# ProtoBricks_8x8.net
KiCad netlist of a schematic drawn in EAGLE
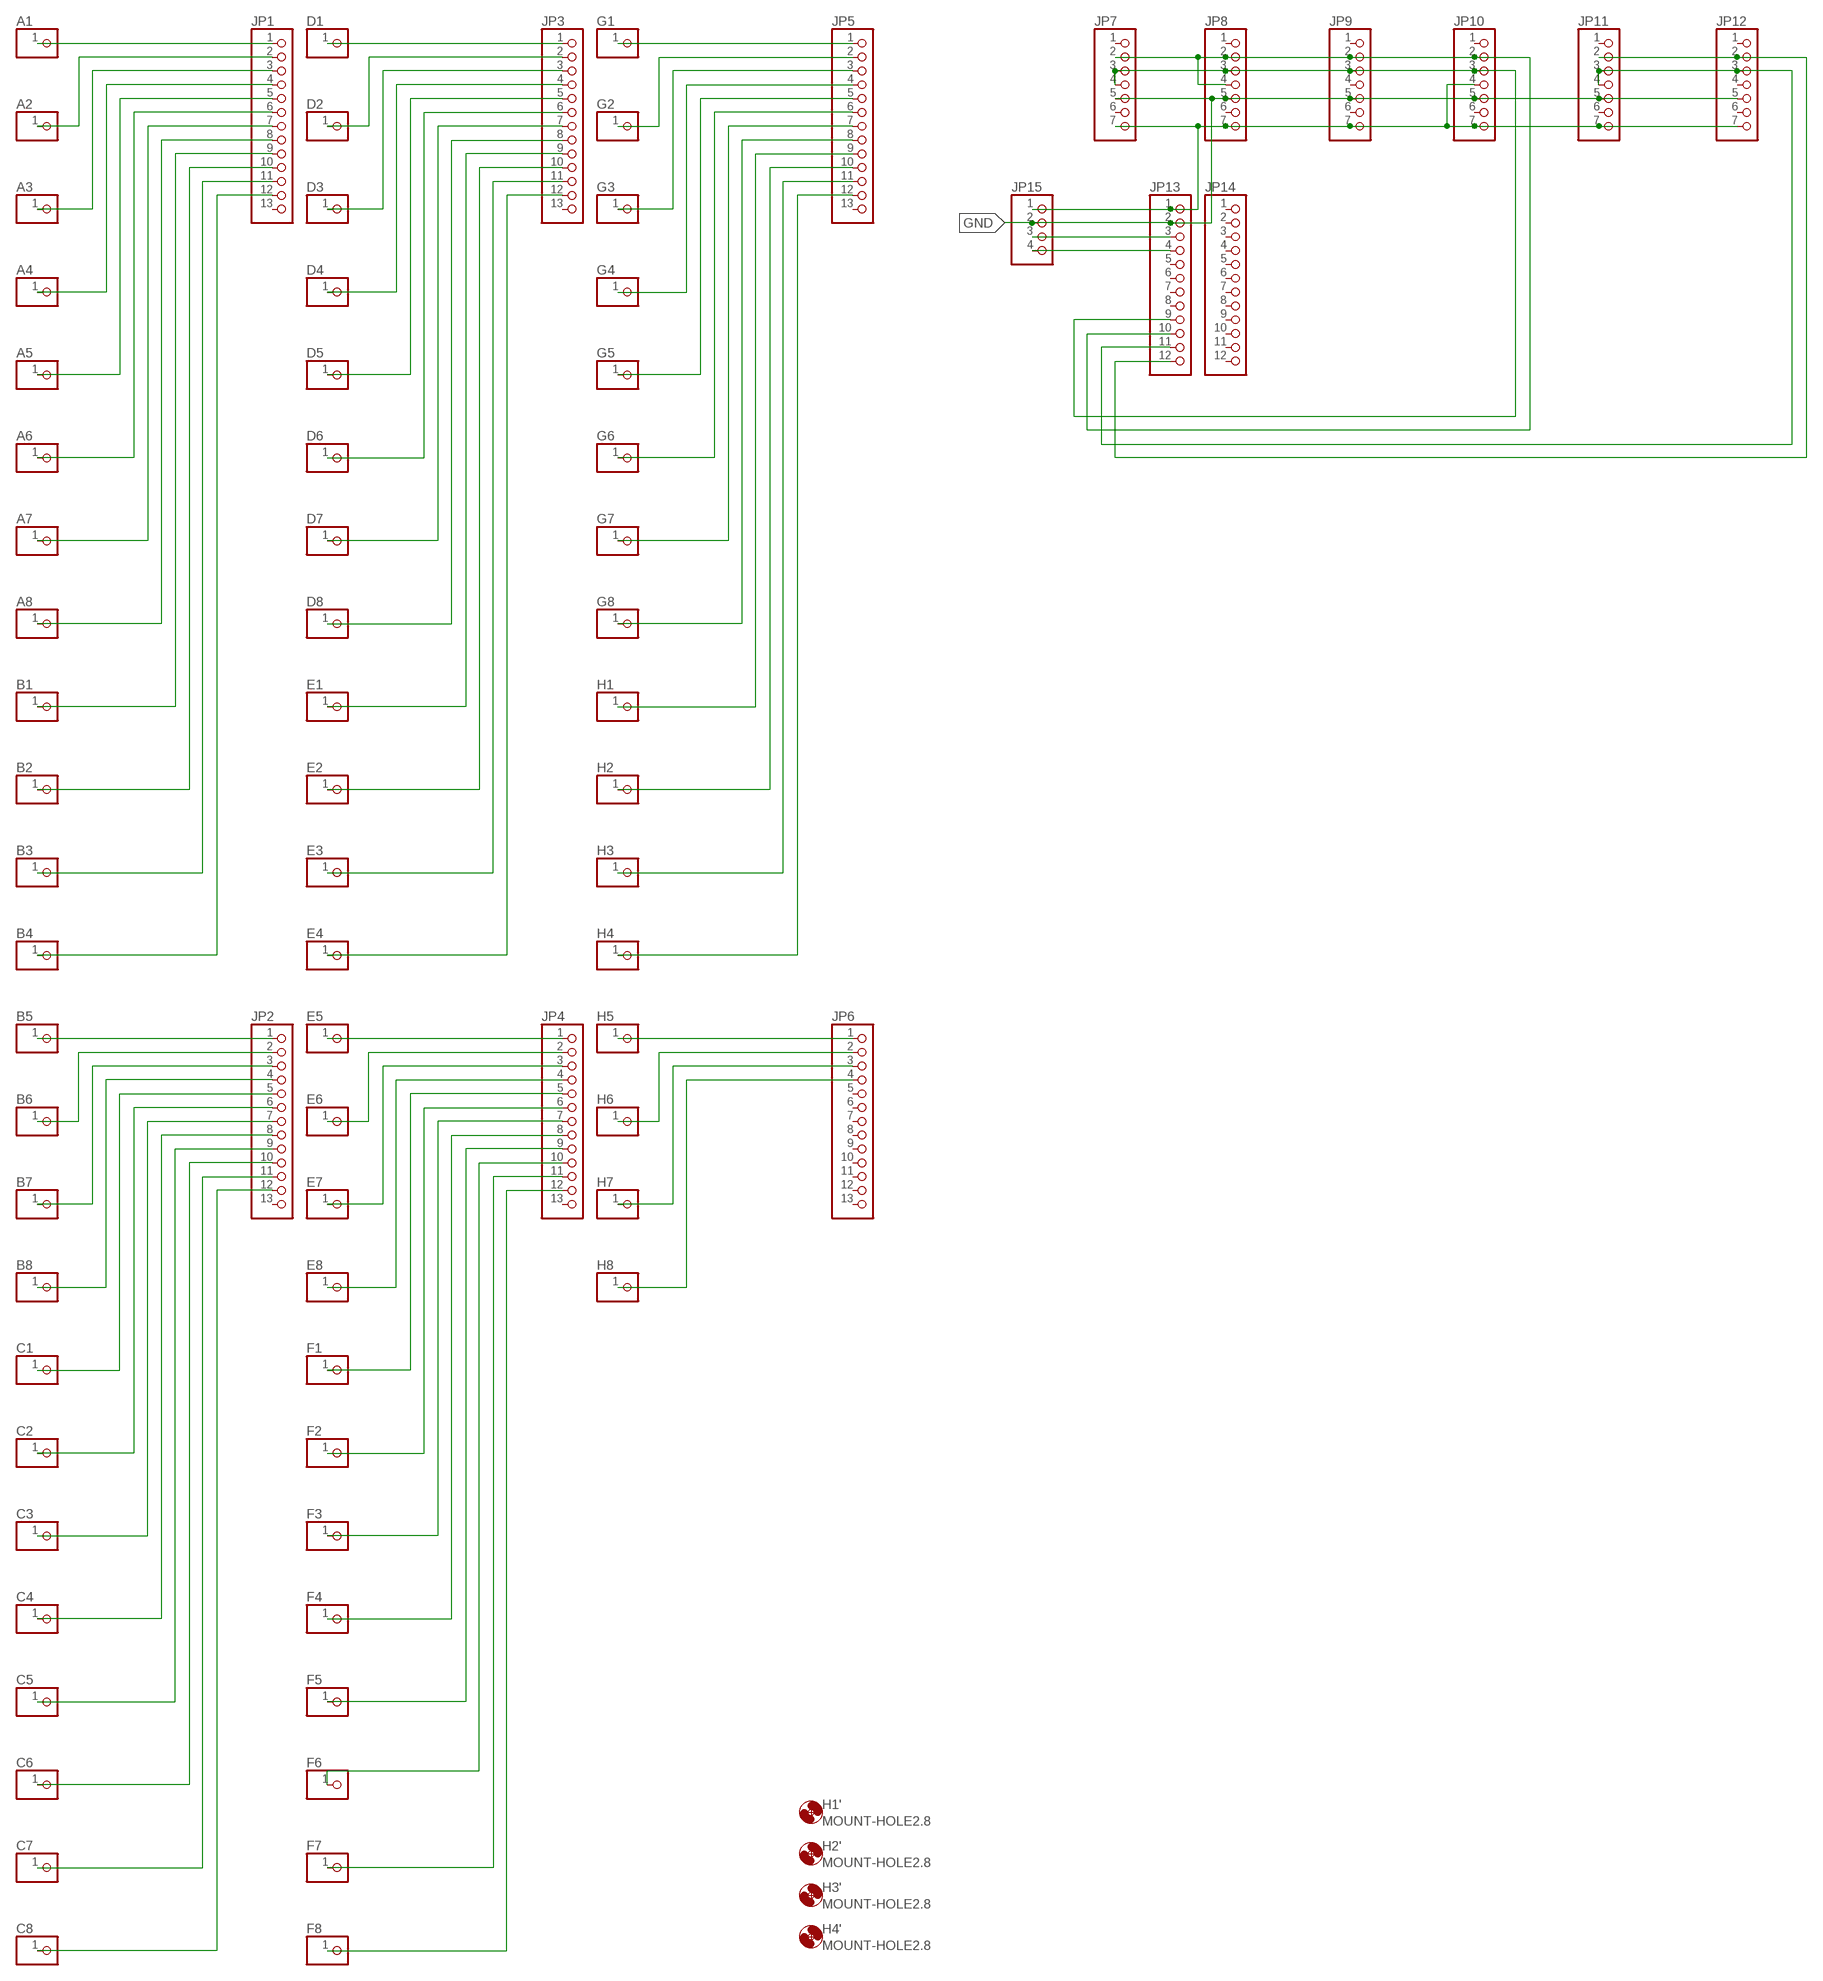
[diagram p0: schematic, sheet 1]

(export (version "E")
  (design (tool "Eeschema 10.0.6"))
  (components
    (comp (ref "A1")
      (value "PINHD-1X1")
      (footprint "eagle-import:1X01")
      (libsource (lib "eagle-import") (part "PINHD-1X1"))
    )
    (comp (ref "A2")
      (value "PINHD-1X1")
      (footprint "eagle-import:1X01")
      (libsource (lib "eagle-import") (part "PINHD-1X1"))
    )
    (comp (ref "A3")
      (value "PINHD-1X1")
      (footprint "eagle-import:1X01")
      (libsource (lib "eagle-import") (part "PINHD-1X1"))
    )
    (comp (ref "A4")
      (value "PINHD-1X1")
      (footprint "eagle-import:1X01")
      (libsource (lib "eagle-import") (part "PINHD-1X1"))
    )
    (comp (ref "A5")
      (value "PINHD-1X1")
      (footprint "eagle-import:1X01")
      (libsource (lib "eagle-import") (part "PINHD-1X1"))
    )
    (comp (ref "A6")
      (value "PINHD-1X1")
      (footprint "eagle-import:1X01")
      (libsource (lib "eagle-import") (part "PINHD-1X1"))
    )
    (comp (ref "A7")
      (value "PINHD-1X1")
      (footprint "eagle-import:1X01")
      (libsource (lib "eagle-import") (part "PINHD-1X1"))
    )
    (comp (ref "A8")
      (value "PINHD-1X1")
      (footprint "eagle-import:1X01")
      (libsource (lib "eagle-import") (part "PINHD-1X1"))
    )
    (comp (ref "B1")
      (value "PINHD-1X1")
      (footprint "eagle-import:1X01")
      (libsource (lib "eagle-import") (part "PINHD-1X1"))
    )
    (comp (ref "B2")
      (value "PINHD-1X1")
      (footprint "eagle-import:1X01")
      (libsource (lib "eagle-import") (part "PINHD-1X1"))
    )
    (comp (ref "B3")
      (value "PINHD-1X1")
      (footprint "eagle-import:1X01")
      (libsource (lib "eagle-import") (part "PINHD-1X1"))
    )
    (comp (ref "B4")
      (value "PINHD-1X1")
      (footprint "eagle-import:1X01")
      (libsource (lib "eagle-import") (part "PINHD-1X1"))
    )
    (comp (ref "B5")
      (value "PINHD-1X1")
      (footprint "eagle-import:1X01")
      (libsource (lib "eagle-import") (part "PINHD-1X1"))
    )
    (comp (ref "B6")
      (value "PINHD-1X1")
      (footprint "eagle-import:1X01")
      (libsource (lib "eagle-import") (part "PINHD-1X1"))
    )
    (comp (ref "B7")
      (value "PINHD-1X1")
      (footprint "eagle-import:1X01")
      (libsource (lib "eagle-import") (part "PINHD-1X1"))
    )
    (comp (ref "B8")
      (value "PINHD-1X1")
      (footprint "eagle-import:1X01")
      (libsource (lib "eagle-import") (part "PINHD-1X1"))
    )
    (comp (ref "C1")
      (value "PINHD-1X1")
      (footprint "eagle-import:1X01")
      (libsource (lib "eagle-import") (part "PINHD-1X1"))
    )
    (comp (ref "C2")
      (value "PINHD-1X1")
      (footprint "eagle-import:1X01")
      (libsource (lib "eagle-import") (part "PINHD-1X1"))
    )
    (comp (ref "C3")
      (value "PINHD-1X1")
      (footprint "eagle-import:1X01")
      (libsource (lib "eagle-import") (part "PINHD-1X1"))
    )
    (comp (ref "C4")
      (value "PINHD-1X1")
      (footprint "eagle-import:1X01")
      (libsource (lib "eagle-import") (part "PINHD-1X1"))
    )
    (comp (ref "C5")
      (value "PINHD-1X1")
      (footprint "eagle-import:1X01")
      (libsource (lib "eagle-import") (part "PINHD-1X1"))
    )
    (comp (ref "C6")
      (value "PINHD-1X1")
      (footprint "eagle-import:1X01")
      (libsource (lib "eagle-import") (part "PINHD-1X1"))
    )
    (comp (ref "C7")
      (value "PINHD-1X1")
      (footprint "eagle-import:1X01")
      (libsource (lib "eagle-import") (part "PINHD-1X1"))
    )
    (comp (ref "C8")
      (value "PINHD-1X1")
      (footprint "eagle-import:1X01")
      (libsource (lib "eagle-import") (part "PINHD-1X1"))
    )
    (comp (ref "D1")
      (value "PINHD-1X1")
      (footprint "eagle-import:1X01")
      (libsource (lib "eagle-import") (part "PINHD-1X1"))
    )
    (comp (ref "D2")
      (value "PINHD-1X1")
      (footprint "eagle-import:1X01")
      (libsource (lib "eagle-import") (part "PINHD-1X1"))
    )
    (comp (ref "D3")
      (value "PINHD-1X1")
      (footprint "eagle-import:1X01")
      (libsource (lib "eagle-import") (part "PINHD-1X1"))
    )
    (comp (ref "D4")
      (value "PINHD-1X1")
      (footprint "eagle-import:1X01")
      (libsource (lib "eagle-import") (part "PINHD-1X1"))
    )
    (comp (ref "D5")
      (value "PINHD-1X1")
      (footprint "eagle-import:1X01")
      (libsource (lib "eagle-import") (part "PINHD-1X1"))
    )
    (comp (ref "D6")
      (value "PINHD-1X1")
      (footprint "eagle-import:1X01")
      (libsource (lib "eagle-import") (part "PINHD-1X1"))
    )
    (comp (ref "D7")
      (value "PINHD-1X1")
      (footprint "eagle-import:1X01")
      (libsource (lib "eagle-import") (part "PINHD-1X1"))
    )
    (comp (ref "D8")
      (value "PINHD-1X1")
      (footprint "eagle-import:1X01")
      (libsource (lib "eagle-import") (part "PINHD-1X1"))
    )
    (comp (ref "E1")
      (value "PINHD-1X1")
      (footprint "eagle-import:1X01")
      (libsource (lib "eagle-import") (part "PINHD-1X1"))
    )
    (comp (ref "E2")
      (value "PINHD-1X1")
      (footprint "eagle-import:1X01")
      (libsource (lib "eagle-import") (part "PINHD-1X1"))
    )
    (comp (ref "E3")
      (value "PINHD-1X1")
      (footprint "eagle-import:1X01")
      (libsource (lib "eagle-import") (part "PINHD-1X1"))
    )
    (comp (ref "E4")
      (value "PINHD-1X1")
      (footprint "eagle-import:1X01")
      (libsource (lib "eagle-import") (part "PINHD-1X1"))
    )
    (comp (ref "E5")
      (value "PINHD-1X1")
      (footprint "eagle-import:1X01")
      (libsource (lib "eagle-import") (part "PINHD-1X1"))
    )
    (comp (ref "E6")
      (value "PINHD-1X1")
      (footprint "eagle-import:1X01")
      (libsource (lib "eagle-import") (part "PINHD-1X1"))
    )
    (comp (ref "E7")
      (value "PINHD-1X1")
      (footprint "eagle-import:1X01")
      (libsource (lib "eagle-import") (part "PINHD-1X1"))
    )
    (comp (ref "E8")
      (value "PINHD-1X1")
      (footprint "eagle-import:1X01")
      (libsource (lib "eagle-import") (part "PINHD-1X1"))
    )
    (comp (ref "F1")
      (value "PINHD-1X1")
      (footprint "eagle-import:1X01")
      (libsource (lib "eagle-import") (part "PINHD-1X1"))
    )
    (comp (ref "F2")
      (value "PINHD-1X1")
      (footprint "eagle-import:1X01")
      (libsource (lib "eagle-import") (part "PINHD-1X1"))
    )
    (comp (ref "F3")
      (value "PINHD-1X1")
      (footprint "eagle-import:1X01")
      (libsource (lib "eagle-import") (part "PINHD-1X1"))
    )
    (comp (ref "F4")
      (value "PINHD-1X1")
      (footprint "eagle-import:1X01")
      (libsource (lib "eagle-import") (part "PINHD-1X1"))
    )
    (comp (ref "F5")
      (value "PINHD-1X1")
      (footprint "eagle-import:1X01")
      (libsource (lib "eagle-import") (part "PINHD-1X1"))
    )
    (comp (ref "F6")
      (value "PINHD-1X1")
      (footprint "eagle-import:1X01")
      (libsource (lib "eagle-import") (part "PINHD-1X1"))
    )
    (comp (ref "F7")
      (value "PINHD-1X1")
      (footprint "eagle-import:1X01")
      (libsource (lib "eagle-import") (part "PINHD-1X1"))
    )
    (comp (ref "F8")
      (value "PINHD-1X1")
      (footprint "eagle-import:1X01")
      (libsource (lib "eagle-import") (part "PINHD-1X1"))
    )
    (comp (ref "G1")
      (value "PINHD-1X1")
      (footprint "eagle-import:1X01")
      (libsource (lib "eagle-import") (part "PINHD-1X1"))
    )
    (comp (ref "G2")
      (value "PINHD-1X1")
      (footprint "eagle-import:1X01")
      (libsource (lib "eagle-import") (part "PINHD-1X1"))
    )
    (comp (ref "G3")
      (value "PINHD-1X1")
      (footprint "eagle-import:1X01")
      (libsource (lib "eagle-import") (part "PINHD-1X1"))
    )
    (comp (ref "G4")
      (value "PINHD-1X1")
      (footprint "eagle-import:1X01")
      (libsource (lib "eagle-import") (part "PINHD-1X1"))
    )
    (comp (ref "G5")
      (value "PINHD-1X1")
      (footprint "eagle-import:1X01")
      (libsource (lib "eagle-import") (part "PINHD-1X1"))
    )
    (comp (ref "G6")
      (value "PINHD-1X1")
      (footprint "eagle-import:1X01")
      (libsource (lib "eagle-import") (part "PINHD-1X1"))
    )
    (comp (ref "G7")
      (value "PINHD-1X1")
      (footprint "eagle-import:1X01")
      (libsource (lib "eagle-import") (part "PINHD-1X1"))
    )
    (comp (ref "G8")
      (value "PINHD-1X1")
      (footprint "eagle-import:1X01")
      (libsource (lib "eagle-import") (part "PINHD-1X1"))
    )
    (comp (ref "H1")
      (value "PINHD-1X1")
      (footprint "eagle-import:1X01")
      (libsource (lib "eagle-import") (part "PINHD-1X1"))
    )
    (comp (ref "H1'")
      (value "MOUNT-HOLE2.8")
      (footprint "eagle-import:2,8")
      (libsource (lib "eagle-import") (part "MOUNT-HOLE2.8"))
    )
    (comp (ref "H2")
      (value "PINHD-1X1")
      (footprint "eagle-import:1X01")
      (libsource (lib "eagle-import") (part "PINHD-1X1"))
    )
    (comp (ref "H2'")
      (value "MOUNT-HOLE2.8")
      (footprint "eagle-import:2,8")
      (libsource (lib "eagle-import") (part "MOUNT-HOLE2.8"))
    )
    (comp (ref "H3")
      (value "PINHD-1X1")
      (footprint "eagle-import:1X01")
      (libsource (lib "eagle-import") (part "PINHD-1X1"))
    )
    (comp (ref "H3'")
      (value "MOUNT-HOLE2.8")
      (footprint "eagle-import:2,8")
      (libsource (lib "eagle-import") (part "MOUNT-HOLE2.8"))
    )
    (comp (ref "H4")
      (value "PINHD-1X1")
      (footprint "eagle-import:1X01")
      (libsource (lib "eagle-import") (part "PINHD-1X1"))
    )
    (comp (ref "H4'")
      (value "MOUNT-HOLE2.8")
      (footprint "eagle-import:2,8")
      (libsource (lib "eagle-import") (part "MOUNT-HOLE2.8"))
    )
    (comp (ref "H5")
      (value "PINHD-1X1")
      (footprint "eagle-import:1X01")
      (libsource (lib "eagle-import") (part "PINHD-1X1"))
    )
    (comp (ref "H6")
      (value "PINHD-1X1")
      (footprint "eagle-import:1X01")
      (libsource (lib "eagle-import") (part "PINHD-1X1"))
    )
    (comp (ref "H7")
      (value "PINHD-1X1")
      (footprint "eagle-import:1X01")
      (libsource (lib "eagle-import") (part "PINHD-1X1"))
    )
    (comp (ref "H8")
      (value "PINHD-1X1")
      (footprint "eagle-import:1X01")
      (libsource (lib "eagle-import") (part "PINHD-1X1"))
    )
    (comp (ref "JP1")
      (value "PINHD-1X13")
      (footprint "eagle-import:1X13")
      (libsource (lib "eagle-import") (part "PINHD-1X13"))
    )
    (comp (ref "JP2")
      (value "PINHD-1X13")
      (footprint "eagle-import:1X13")
      (libsource (lib "eagle-import") (part "PINHD-1X13"))
    )
    (comp (ref "JP3")
      (value "PINHD-1X13")
      (footprint "eagle-import:1X13")
      (libsource (lib "eagle-import") (part "PINHD-1X13"))
    )
    (comp (ref "JP4")
      (value "PINHD-1X13")
      (footprint "eagle-import:1X13")
      (libsource (lib "eagle-import") (part "PINHD-1X13"))
    )
    (comp (ref "JP5")
      (value "PINHD-1X13")
      (footprint "eagle-import:1X13")
      (libsource (lib "eagle-import") (part "PINHD-1X13"))
    )
    (comp (ref "JP6")
      (value "PINHD-1X13")
      (footprint "eagle-import:1X13")
      (libsource (lib "eagle-import") (part "PINHD-1X13"))
    )
    (comp (ref "JP7")
      (value "PINHD-1X7")
      (footprint "eagle-import:1X07")
      (libsource (lib "eagle-import") (part "PINHD-1X7"))
    )
    (comp (ref "JP8")
      (value "PINHD-1X7")
      (footprint "eagle-import:1X07")
      (libsource (lib "eagle-import") (part "PINHD-1X7"))
    )
    (comp (ref "JP9")
      (value "PINHD-1X7")
      (footprint "eagle-import:1X07")
      (libsource (lib "eagle-import") (part "PINHD-1X7"))
    )
    (comp (ref "JP10")
      (value "PINHD-1X7")
      (footprint "eagle-import:1X07")
      (libsource (lib "eagle-import") (part "PINHD-1X7"))
    )
    (comp (ref "JP11")
      (value "PINHD-1X7")
      (footprint "eagle-import:1X07")
      (libsource (lib "eagle-import") (part "PINHD-1X7"))
    )
    (comp (ref "JP12")
      (value "PINHD-1X7")
      (footprint "eagle-import:1X07")
      (libsource (lib "eagle-import") (part "PINHD-1X7"))
    )
    (comp (ref "JP13")
      (value "PINHD-1X12")
      (footprint "eagle-import:1X12")
      (libsource (lib "eagle-import") (part "PINHD-1X12"))
    )
    (comp (ref "JP14")
      (value "PINHD-1X12")
      (footprint "eagle-import:1X12")
      (libsource (lib "eagle-import") (part "PINHD-1X12"))
    )
    (comp (ref "JP15")
      (value "PINHD-1X4")
      (footprint "eagle-import:1X04")
      (libsource (lib "eagle-import") (part "PINHD-1X4"))
    )
  )
  (nets
    (net (code "1") (name "GND") (class "Default")
      (node (ref "JP10") (pin "5") (pinfunction "5_5") (pintype "passive"))
      (node (ref "JP11") (pin "5") (pinfunction "5_5") (pintype "passive"))
      (node (ref "JP12") (pin "5") (pinfunction "5_5") (pintype "passive"))
      (node (ref "JP13") (pin "2") (pinfunction "2_2") (pintype "passive"))
      (node (ref "JP15") (pin "2") (pinfunction "2_2") (pintype "passive"))
      (node (ref "JP7") (pin "5") (pinfunction "5_5") (pintype "passive"))
      (node (ref "JP8") (pin "5") (pinfunction "5_5") (pintype "passive"))
      (node (ref "JP9") (pin "5") (pinfunction "5_5") (pintype "passive"))
    )
    (net (code "2") (name "Net-(A1-Pad1)") (class "Default")
      (node (ref "A1") (pin "1") (pinfunction "1_1") (pintype "passive"))
      (node (ref "JP1") (pin "1") (pinfunction "1_1") (pintype "passive"))
    )
    (net (code "3") (name "Net-(A2-Pad1)") (class "Default")
      (node (ref "A2") (pin "1") (pinfunction "1_1") (pintype "passive"))
      (node (ref "JP1") (pin "2") (pinfunction "2_2") (pintype "passive"))
    )
    (net (code "4") (name "Net-(A3-Pad1)") (class "Default")
      (node (ref "A3") (pin "1") (pinfunction "1_1") (pintype "passive"))
      (node (ref "JP1") (pin "3") (pinfunction "3_3") (pintype "passive"))
    )
    (net (code "5") (name "Net-(A4-Pad1)") (class "Default")
      (node (ref "A4") (pin "1") (pinfunction "1_1") (pintype "passive"))
      (node (ref "JP1") (pin "4") (pinfunction "4_4") (pintype "passive"))
    )
    (net (code "6") (name "Net-(A5-Pad1)") (class "Default")
      (node (ref "A5") (pin "1") (pinfunction "1_1") (pintype "passive"))
      (node (ref "JP1") (pin "5") (pinfunction "5_5") (pintype "passive"))
    )
    (net (code "7") (name "Net-(A6-Pad1)") (class "Default")
      (node (ref "A6") (pin "1") (pinfunction "1_1") (pintype "passive"))
      (node (ref "JP1") (pin "6") (pinfunction "6_6") (pintype "passive"))
    )
    (net (code "8") (name "Net-(A7-Pad1)") (class "Default")
      (node (ref "A7") (pin "1") (pinfunction "1_1") (pintype "passive"))
      (node (ref "JP1") (pin "7") (pinfunction "7_7") (pintype "passive"))
    )
    (net (code "9") (name "Net-(A8-Pad1)") (class "Default")
      (node (ref "A8") (pin "1") (pinfunction "1_1") (pintype "passive"))
      (node (ref "JP1") (pin "8") (pinfunction "8_8") (pintype "passive"))
    )
    (net (code "10") (name "Net-(B1-Pad1)") (class "Default")
      (node (ref "B1") (pin "1") (pinfunction "1_1") (pintype "passive"))
      (node (ref "JP1") (pin "9") (pinfunction "9_9") (pintype "passive"))
    )
    (net (code "11") (name "Net-(B2-Pad1)") (class "Default")
      (node (ref "B2") (pin "1") (pinfunction "1_1") (pintype "passive"))
      (node (ref "JP1") (pin "10") (pinfunction "10_10") (pintype "passive"))
    )
    (net (code "12") (name "Net-(B3-Pad1)") (class "Default")
      (node (ref "B3") (pin "1") (pinfunction "1_1") (pintype "passive"))
      (node (ref "JP1") (pin "11") (pinfunction "11_11") (pintype "passive"))
    )
    (net (code "13") (name "Net-(B4-Pad1)") (class "Default")
      (node (ref "B4") (pin "1") (pinfunction "1_1") (pintype "passive"))
      (node (ref "JP1") (pin "12") (pinfunction "12_12") (pintype "passive"))
    )
    (net (code "14") (name "Net-(B5-Pad1)") (class "Default")
      (node (ref "B5") (pin "1") (pinfunction "1_1") (pintype "passive"))
      (node (ref "JP2") (pin "1") (pinfunction "1_1") (pintype "passive"))
    )
    (net (code "15") (name "Net-(B6-Pad1)") (class "Default")
      (node (ref "B6") (pin "1") (pinfunction "1_1") (pintype "passive"))
      (node (ref "JP2") (pin "2") (pinfunction "2_2") (pintype "passive"))
    )
    (net (code "16") (name "Net-(B7-Pad1)") (class "Default")
      (node (ref "B7") (pin "1") (pinfunction "1_1") (pintype "passive"))
      (node (ref "JP2") (pin "3") (pinfunction "3_3") (pintype "passive"))
    )
    (net (code "17") (name "Net-(B8-Pad1)") (class "Default")
      (node (ref "B8") (pin "1") (pinfunction "1_1") (pintype "passive"))
      (node (ref "JP2") (pin "4") (pinfunction "4_4") (pintype "passive"))
    )
    (net (code "18") (name "Net-(C1-Pad1)") (class "Default")
      (node (ref "C1") (pin "1") (pinfunction "1_1") (pintype "passive"))
      (node (ref "JP2") (pin "5") (pinfunction "5_5") (pintype "passive"))
    )
    (net (code "19") (name "Net-(C2-Pad1)") (class "Default")
      (node (ref "C2") (pin "1") (pinfunction "1_1") (pintype "passive"))
      (node (ref "JP2") (pin "6") (pinfunction "6_6") (pintype "passive"))
    )
    (net (code "20") (name "Net-(C3-Pad1)") (class "Default")
      (node (ref "C3") (pin "1") (pinfunction "1_1") (pintype "passive"))
      (node (ref "JP2") (pin "7") (pinfunction "7_7") (pintype "passive"))
    )
    (net (code "21") (name "Net-(C4-Pad1)") (class "Default")
      (node (ref "C4") (pin "1") (pinfunction "1_1") (pintype "passive"))
      (node (ref "JP2") (pin "8") (pinfunction "8_8") (pintype "passive"))
    )
    (net (code "22") (name "Net-(C5-Pad1)") (class "Default")
      (node (ref "C5") (pin "1") (pinfunction "1_1") (pintype "passive"))
      (node (ref "JP2") (pin "9") (pinfunction "9_9") (pintype "passive"))
    )
    (net (code "23") (name "Net-(C6-Pad1)") (class "Default")
      (node (ref "C6") (pin "1") (pinfunction "1_1") (pintype "passive"))
      (node (ref "JP2") (pin "10") (pinfunction "10_10") (pintype "passive"))
    )
    (net (code "24") (name "Net-(C7-Pad1)") (class "Default")
      (node (ref "C7") (pin "1") (pinfunction "1_1") (pintype "passive"))
      (node (ref "JP2") (pin "11") (pinfunction "11_11") (pintype "passive"))
    )
    (net (code "25") (name "Net-(C8-Pad1)") (class "Default")
      (node (ref "C8") (pin "1") (pinfunction "1_1") (pintype "passive"))
      (node (ref "JP2") (pin "12") (pinfunction "12_12") (pintype "passive"))
    )
    (net (code "26") (name "Net-(D1-Pad1)") (class "Default")
      (node (ref "D1") (pin "1") (pinfunction "1_1") (pintype "passive"))
      (node (ref "JP3") (pin "1") (pinfunction "1_1") (pintype "passive"))
    )
    (net (code "27") (name "Net-(D2-Pad1)") (class "Default")
      (node (ref "D2") (pin "1") (pinfunction "1_1") (pintype "passive"))
      (node (ref "JP3") (pin "2") (pinfunction "2_2") (pintype "passive"))
    )
    (net (code "28") (name "Net-(D3-Pad1)") (class "Default")
      (node (ref "D3") (pin "1") (pinfunction "1_1") (pintype "passive"))
      (node (ref "JP3") (pin "3") (pinfunction "3_3") (pintype "passive"))
    )
    (net (code "29") (name "Net-(D4-Pad1)") (class "Default")
      (node (ref "D4") (pin "1") (pinfunction "1_1") (pintype "passive"))
      (node (ref "JP3") (pin "4") (pinfunction "4_4") (pintype "passive"))
    )
    (net (code "30") (name "Net-(D5-Pad1)") (class "Default")
      (node (ref "D5") (pin "1") (pinfunction "1_1") (pintype "passive"))
      (node (ref "JP3") (pin "5") (pinfunction "5_5") (pintype "passive"))
    )
    (net (code "31") (name "Net-(D6-Pad1)") (class "Default")
      (node (ref "D6") (pin "1") (pinfunction "1_1") (pintype "passive"))
      (node (ref "JP3") (pin "6") (pinfunction "6_6") (pintype "passive"))
    )
    (net (code "32") (name "Net-(D7-Pad1)") (class "Default")
      (node (ref "D7") (pin "1") (pinfunction "1_1") (pintype "passive"))
      (node (ref "JP3") (pin "7") (pinfunction "7_7") (pintype "passive"))
    )
    (net (code "33") (name "Net-(D8-Pad1)") (class "Default")
      (node (ref "D8") (pin "1") (pinfunction "1_1") (pintype "passive"))
      (node (ref "JP3") (pin "8") (pinfunction "8_8") (pintype "passive"))
    )
    (net (code "34") (name "Net-(E1-Pad1)") (class "Default")
      (node (ref "E1") (pin "1") (pinfunction "1_1") (pintype "passive"))
      (node (ref "JP3") (pin "9") (pinfunction "9_9") (pintype "passive"))
    )
    (net (code "35") (name "Net-(E2-Pad1)") (class "Default")
      (node (ref "E2") (pin "1") (pinfunction "1_1") (pintype "passive"))
      (node (ref "JP3") (pin "10") (pinfunction "10_10") (pintype "passive"))
    )
    (net (code "36") (name "Net-(E3-Pad1)") (class "Default")
      (node (ref "E3") (pin "1") (pinfunction "1_1") (pintype "passive"))
      (node (ref "JP3") (pin "11") (pinfunction "11_11") (pintype "passive"))
    )
    (net (code "37") (name "Net-(E4-Pad1)") (class "Default")
      (node (ref "E4") (pin "1") (pinfunction "1_1") (pintype "passive"))
      (node (ref "JP3") (pin "12") (pinfunction "12_12") (pintype "passive"))
    )
    (net (code "38") (name "Net-(E5-Pad1)") (class "Default")
      (node (ref "E5") (pin "1") (pinfunction "1_1") (pintype "passive"))
      (node (ref "JP4") (pin "1") (pinfunction "1_1") (pintype "passive"))
    )
    (net (code "39") (name "Net-(E6-Pad1)") (class "Default")
      (node (ref "E6") (pin "1") (pinfunction "1_1") (pintype "passive"))
      (node (ref "JP4") (pin "2") (pinfunction "2_2") (pintype "passive"))
    )
    (net (code "40") (name "Net-(E7-Pad1)") (class "Default")
      (node (ref "E7") (pin "1") (pinfunction "1_1") (pintype "passive"))
      (node (ref "JP4") (pin "3") (pinfunction "3_3") (pintype "passive"))
    )
    (net (code "41") (name "Net-(E8-Pad1)") (class "Default")
      (node (ref "E8") (pin "1") (pinfunction "1_1") (pintype "passive"))
      (node (ref "JP4") (pin "4") (pinfunction "4_4") (pintype "passive"))
    )
    (net (code "42") (name "Net-(F1-Pad1)") (class "Default")
      (node (ref "F1") (pin "1") (pinfunction "1_1") (pintype "passive"))
      (node (ref "JP4") (pin "5") (pinfunction "5_5") (pintype "passive"))
    )
    (net (code "43") (name "Net-(F2-Pad1)") (class "Default")
      (node (ref "F2") (pin "1") (pinfunction "1_1") (pintype "passive"))
      (node (ref "JP4") (pin "6") (pinfunction "6_6") (pintype "passive"))
    )
    (net (code "44") (name "Net-(F3-Pad1)") (class "Default")
      (node (ref "F3") (pin "1") (pinfunction "1_1") (pintype "passive"))
      (node (ref "JP4") (pin "7") (pinfunction "7_7") (pintype "passive"))
    )
    (net (code "45") (name "Net-(F4-Pad1)") (class "Default")
      (node (ref "F4") (pin "1") (pinfunction "1_1") (pintype "passive"))
      (node (ref "JP4") (pin "8") (pinfunction "8_8") (pintype "passive"))
    )
    (net (code "46") (name "Net-(F5-Pad1)") (class "Default")
      (node (ref "F5") (pin "1") (pinfunction "1_1") (pintype "passive"))
      (node (ref "JP4") (pin "9") (pinfunction "9_9") (pintype "passive"))
    )
    (net (code "47") (name "Net-(F6-Pad1)") (class "Default")
      (node (ref "F6") (pin "1") (pinfunction "1_1") (pintype "passive"))
      (node (ref "JP4") (pin "10") (pinfunction "10_10") (pintype "passive"))
    )
    (net (code "48") (name "Net-(F7-Pad1)") (class "Default")
      (node (ref "F7") (pin "1") (pinfunction "1_1") (pintype "passive"))
      (node (ref "JP4") (pin "11") (pinfunction "11_11") (pintype "passive"))
    )
    (net (code "49") (name "Net-(F8-Pad1)") (class "Default")
      (node (ref "F8") (pin "1") (pinfunction "1_1") (pintype "passive"))
      (node (ref "JP4") (pin "12") (pinfunction "12_12") (pintype "passive"))
    )
    (net (code "50") (name "Net-(G1-Pad1)") (class "Default")
      (node (ref "G1") (pin "1") (pinfunction "1_1") (pintype "passive"))
      (node (ref "JP5") (pin "1") (pinfunction "1_1") (pintype "passive"))
    )
    (net (code "51") (name "Net-(G2-Pad1)") (class "Default")
      (node (ref "G2") (pin "1") (pinfunction "1_1") (pintype "passive"))
      (node (ref "JP5") (pin "2") (pinfunction "2_2") (pintype "passive"))
    )
    (net (code "52") (name "Net-(G3-Pad1)") (class "Default")
      (node (ref "G3") (pin "1") (pinfunction "1_1") (pintype "passive"))
      (node (ref "JP5") (pin "3") (pinfunction "3_3") (pintype "passive"))
    )
    (net (code "53") (name "Net-(G4-Pad1)") (class "Default")
      (node (ref "G4") (pin "1") (pinfunction "1_1") (pintype "passive"))
      (node (ref "JP5") (pin "4") (pinfunction "4_4") (pintype "passive"))
    )
    (net (code "54") (name "Net-(G5-Pad1)") (class "Default")
      (node (ref "G5") (pin "1") (pinfunction "1_1") (pintype "passive"))
      (node (ref "JP5") (pin "5") (pinfunction "5_5") (pintype "passive"))
    )
    (net (code "55") (name "Net-(G6-Pad1)") (class "Default")
      (node (ref "G6") (pin "1") (pinfunction "1_1") (pintype "passive"))
      (node (ref "JP5") (pin "6") (pinfunction "6_6") (pintype "passive"))
    )
    (net (code "56") (name "Net-(G7-Pad1)") (class "Default")
      (node (ref "G7") (pin "1") (pinfunction "1_1") (pintype "passive"))
      (node (ref "JP5") (pin "7") (pinfunction "7_7") (pintype "passive"))
    )
    (net (code "57") (name "Net-(G8-Pad1)") (class "Default")
      (node (ref "G8") (pin "1") (pinfunction "1_1") (pintype "passive"))
      (node (ref "JP5") (pin "8") (pinfunction "8_8") (pintype "passive"))
    )
    (net (code "58") (name "Net-(H1-Pad1)") (class "Default")
      (node (ref "H1") (pin "1") (pinfunction "1_1") (pintype "passive"))
      (node (ref "JP5") (pin "9") (pinfunction "9_9") (pintype "passive"))
    )
    (net (code "59") (name "Net-(H2-Pad1)") (class "Default")
      (node (ref "H2") (pin "1") (pinfunction "1_1") (pintype "passive"))
      (node (ref "JP5") (pin "10") (pinfunction "10_10") (pintype "passive"))
    )
    (net (code "60") (name "Net-(H3-Pad1)") (class "Default")
      (node (ref "H3") (pin "1") (pinfunction "1_1") (pintype "passive"))
      (node (ref "JP5") (pin "11") (pinfunction "11_11") (pintype "passive"))
    )
    (net (code "61") (name "Net-(H4-Pad1)") (class "Default")
      (node (ref "H4") (pin "1") (pinfunction "1_1") (pintype "passive"))
      (node (ref "JP5") (pin "12") (pinfunction "12_12") (pintype "passive"))
    )
    (net (code "62") (name "Net-(H5-Pad1)") (class "Default")
      (node (ref "H5") (pin "1") (pinfunction "1_1") (pintype "passive"))
      (node (ref "JP6") (pin "1") (pinfunction "1_1") (pintype "passive"))
    )
    (net (code "63") (name "Net-(H6-Pad1)") (class "Default")
      (node (ref "H6") (pin "1") (pinfunction "1_1") (pintype "passive"))
      (node (ref "JP6") (pin "2") (pinfunction "2_2") (pintype "passive"))
    )
    (net (code "64") (name "Net-(H7-Pad1)") (class "Default")
      (node (ref "H7") (pin "1") (pinfunction "1_1") (pintype "passive"))
      (node (ref "JP6") (pin "3") (pinfunction "3_3") (pintype "passive"))
    )
    (net (code "65") (name "Net-(H8-Pad1)") (class "Default")
      (node (ref "H8") (pin "1") (pinfunction "1_1") (pintype "passive"))
      (node (ref "JP6") (pin "4") (pinfunction "4_4") (pintype "passive"))
    )
    (net (code "66") (name "Net-(JP10-Pad2)") (class "Default")
      (node (ref "JP10") (pin "2") (pinfunction "2_2") (pintype "passive"))
      (node (ref "JP13") (pin "10") (pinfunction "10_10") (pintype "passive"))
      (node (ref "JP7") (pin "2") (pinfunction "2_2") (pintype "passive"))
      (node (ref "JP8") (pin "2") (pinfunction "2_2") (pintype "passive"))
      (node (ref "JP8") (pin "4") (pinfunction "4_4") (pintype "passive"))
      (node (ref "JP9") (pin "2") (pinfunction "2_2") (pintype "passive"))
    )
    (net (code "67") (name "Net-(JP10-Pad3)") (class "Default")
      (node (ref "JP10") (pin "3") (pinfunction "3_3") (pintype "passive"))
      (node (ref "JP13") (pin "9") (pinfunction "9_9") (pintype "passive"))
      (node (ref "JP7") (pin "3") (pinfunction "3_3") (pintype "passive"))
      (node (ref "JP7") (pin "4") (pinfunction "4_4") (pintype "passive"))
      (node (ref "JP8") (pin "3") (pinfunction "3_3") (pintype "passive"))
      (node (ref "JP9") (pin "3") (pinfunction "3_3") (pintype "passive"))
    )
    (net (code "68") (name "Net-(JP10-Pad4)") (class "Default")
      (node (ref "JP10") (pin "4") (pinfunction "4_4") (pintype "passive"))
      (node (ref "JP10") (pin "7") (pinfunction "7_7") (pintype "passive"))
      (node (ref "JP11") (pin "7") (pinfunction "7_7") (pintype "passive"))
      (node (ref "JP12") (pin "7") (pinfunction "7_7") (pintype "passive"))
      (node (ref "JP13") (pin "1") (pinfunction "1_1") (pintype "passive"))
      (node (ref "JP15") (pin "1") (pinfunction "1_1") (pintype "passive"))
      (node (ref "JP7") (pin "7") (pinfunction "7_7") (pintype "passive"))
      (node (ref "JP8") (pin "7") (pinfunction "7_7") (pintype "passive"))
      (node (ref "JP9") (pin "7") (pinfunction "7_7") (pintype "passive"))
    )
    (net (code "69") (name "Net-(JP11-Pad2)") (class "Default")
      (node (ref "JP11") (pin "2") (pinfunction "2_2") (pintype "passive"))
      (node (ref "JP12") (pin "2") (pinfunction "2_2") (pintype "passive"))
      (node (ref "JP13") (pin "12") (pinfunction "12_12") (pintype "passive"))
    )
    (net (code "70") (name "Net-(JP11-Pad3)") (class "Default")
      (node (ref "JP11") (pin "3") (pinfunction "3_3") (pintype "passive"))
      (node (ref "JP11") (pin "4") (pinfunction "4_4") (pintype "passive"))
      (node (ref "JP12") (pin "3") (pinfunction "3_3") (pintype "passive"))
      (node (ref "JP13") (pin "11") (pinfunction "11_11") (pintype "passive"))
    )
    (net (code "71") (name "Net-(JP13-Pad3)") (class "Default")
      (node (ref "JP13") (pin "3") (pinfunction "3_3") (pintype "passive"))
      (node (ref "JP15") (pin "3") (pinfunction "3_3") (pintype "passive"))
    )
    (net (code "72") (name "Net-(JP13-Pad4)") (class "Default")
      (node (ref "JP13") (pin "4") (pinfunction "4_4") (pintype "passive"))
      (node (ref "JP15") (pin "4") (pinfunction "4_4") (pintype "passive"))
    )
    (net (code "73") (name "unconnected-(JP1-Pad13)") (class "Default")
      (node (ref "JP1") (pin "13") (pinfunction "13_13") (pintype "passive"))
    )
    (net (code "74") (name "unconnected-(JP2-Pad13)") (class "Default")
      (node (ref "JP2") (pin "13") (pinfunction "13_13") (pintype "passive"))
    )
    (net (code "75") (name "unconnected-(JP3-Pad13)") (class "Default")
      (node (ref "JP3") (pin "13") (pinfunction "13_13") (pintype "passive"))
    )
    (net (code "76") (name "unconnected-(JP4-Pad13)") (class "Default")
      (node (ref "JP4") (pin "13") (pinfunction "13_13") (pintype "passive"))
    )
    (net (code "77") (name "unconnected-(JP5-Pad13)") (class "Default")
      (node (ref "JP5") (pin "13") (pinfunction "13_13") (pintype "passive"))
    )
    (net (code "78") (name "unconnected-(JP6-Pad5)") (class "Default")
      (node (ref "JP6") (pin "5") (pinfunction "5_5") (pintype "passive"))
    )
    (net (code "79") (name "unconnected-(JP6-Pad6)") (class "Default")
      (node (ref "JP6") (pin "6") (pinfunction "6_6") (pintype "passive"))
    )
    (net (code "80") (name "unconnected-(JP6-Pad7)") (class "Default")
      (node (ref "JP6") (pin "7") (pinfunction "7_7") (pintype "passive"))
    )
    (net (code "81") (name "unconnected-(JP6-Pad8)") (class "Default")
      (node (ref "JP6") (pin "8") (pinfunction "8_8") (pintype "passive"))
    )
    (net (code "82") (name "unconnected-(JP6-Pad9)") (class "Default")
      (node (ref "JP6") (pin "9") (pinfunction "9_9") (pintype "passive"))
    )
    (net (code "83") (name "unconnected-(JP6-Pad10)") (class "Default")
      (node (ref "JP6") (pin "10") (pinfunction "10_10") (pintype "passive"))
    )
    (net (code "84") (name "unconnected-(JP6-Pad11)") (class "Default")
      (node (ref "JP6") (pin "11") (pinfunction "11_11") (pintype "passive"))
    )
    (net (code "85") (name "unconnected-(JP6-Pad12)") (class "Default")
      (node (ref "JP6") (pin "12") (pinfunction "12_12") (pintype "passive"))
    )
    (net (code "86") (name "unconnected-(JP6-Pad13)") (class "Default")
      (node (ref "JP6") (pin "13") (pinfunction "13_13") (pintype "passive"))
    )
    (net (code "87") (name "unconnected-(JP7-Pad1)") (class "Default")
      (node (ref "JP7") (pin "1") (pinfunction "1_1") (pintype "passive"))
    )
    (net (code "88") (name "unconnected-(JP7-Pad6)") (class "Default")
      (node (ref "JP7") (pin "6") (pinfunction "6_6") (pintype "passive"))
    )
    (net (code "89") (name "unconnected-(JP8-Pad1)") (class "Default")
      (node (ref "JP8") (pin "1") (pinfunction "1_1") (pintype "passive"))
    )
    (net (code "90") (name "unconnected-(JP8-Pad6)") (class "Default")
      (node (ref "JP8") (pin "6") (pinfunction "6_6") (pintype "passive"))
    )
    (net (code "91") (name "unconnected-(JP9-Pad1)") (class "Default")
      (node (ref "JP9") (pin "1") (pinfunction "1_1") (pintype "passive"))
    )
    (net (code "92") (name "unconnected-(JP9-Pad4)") (class "Default")
      (node (ref "JP9") (pin "4") (pinfunction "4_4") (pintype "passive"))
    )
    (net (code "93") (name "unconnected-(JP9-Pad6)") (class "Default")
      (node (ref "JP9") (pin "6") (pinfunction "6_6") (pintype "passive"))
    )
    (net (code "94") (name "unconnected-(JP10-Pad1)") (class "Default")
      (node (ref "JP10") (pin "1") (pinfunction "1_1") (pintype "passive"))
    )
    (net (code "95") (name "unconnected-(JP10-Pad6)") (class "Default")
      (node (ref "JP10") (pin "6") (pinfunction "6_6") (pintype "passive"))
    )
    (net (code "96") (name "unconnected-(JP11-Pad1)") (class "Default")
      (node (ref "JP11") (pin "1") (pinfunction "1_1") (pintype "passive"))
    )
    (net (code "97") (name "unconnected-(JP11-Pad6)") (class "Default")
      (node (ref "JP11") (pin "6") (pinfunction "6_6") (pintype "passive"))
    )
    (net (code "98") (name "unconnected-(JP12-Pad1)") (class "Default")
      (node (ref "JP12") (pin "1") (pinfunction "1_1") (pintype "passive"))
    )
    (net (code "99") (name "unconnected-(JP12-Pad4)") (class "Default")
      (node (ref "JP12") (pin "4") (pinfunction "4_4") (pintype "passive"))
    )
    (net (code "100") (name "unconnected-(JP12-Pad6)") (class "Default")
      (node (ref "JP12") (pin "6") (pinfunction "6_6") (pintype "passive"))
    )
    (net (code "101") (name "unconnected-(JP13-Pad5)") (class "Default")
      (node (ref "JP13") (pin "5") (pinfunction "5_5") (pintype "passive"))
    )
    (net (code "102") (name "unconnected-(JP13-Pad6)") (class "Default")
      (node (ref "JP13") (pin "6") (pinfunction "6_6") (pintype "passive"))
    )
    (net (code "103") (name "unconnected-(JP13-Pad7)") (class "Default")
      (node (ref "JP13") (pin "7") (pinfunction "7_7") (pintype "passive"))
    )
    (net (code "104") (name "unconnected-(JP13-Pad8)") (class "Default")
      (node (ref "JP13") (pin "8") (pinfunction "8_8") (pintype "passive"))
    )
    (net (code "105") (name "unconnected-(JP14-Pad1)") (class "Default")
      (node (ref "JP14") (pin "1") (pinfunction "1_1") (pintype "passive"))
    )
    (net (code "106") (name "unconnected-(JP14-Pad2)") (class "Default")
      (node (ref "JP14") (pin "2") (pinfunction "2_2") (pintype "passive"))
    )
    (net (code "107") (name "unconnected-(JP14-Pad3)") (class "Default")
      (node (ref "JP14") (pin "3") (pinfunction "3_3") (pintype "passive"))
    )
    (net (code "108") (name "unconnected-(JP14-Pad4)") (class "Default")
      (node (ref "JP14") (pin "4") (pinfunction "4_4") (pintype "passive"))
    )
    (net (code "109") (name "unconnected-(JP14-Pad5)") (class "Default")
      (node (ref "JP14") (pin "5") (pinfunction "5_5") (pintype "passive"))
    )
    (net (code "110") (name "unconnected-(JP14-Pad6)") (class "Default")
      (node (ref "JP14") (pin "6") (pinfunction "6_6") (pintype "passive"))
    )
    (net (code "111") (name "unconnected-(JP14-Pad7)") (class "Default")
      (node (ref "JP14") (pin "7") (pinfunction "7_7") (pintype "passive"))
    )
    (net (code "112") (name "unconnected-(JP14-Pad8)") (class "Default")
      (node (ref "JP14") (pin "8") (pinfunction "8_8") (pintype "passive"))
    )
    (net (code "113") (name "unconnected-(JP14-Pad9)") (class "Default")
      (node (ref "JP14") (pin "9") (pinfunction "9_9") (pintype "passive"))
    )
    (net (code "114") (name "unconnected-(JP14-Pad10)") (class "Default")
      (node (ref "JP14") (pin "10") (pinfunction "10_10") (pintype "passive"))
    )
    (net (code "115") (name "unconnected-(JP14-Pad11)") (class "Default")
      (node (ref "JP14") (pin "11") (pinfunction "11_11") (pintype "passive"))
    )
    (net (code "116") (name "unconnected-(JP14-Pad12)") (class "Default")
      (node (ref "JP14") (pin "12") (pinfunction "12_12") (pintype "passive"))
    )
  )
)
